# Main.net
KiCad netlist of a schematic drawn in Altium Designer
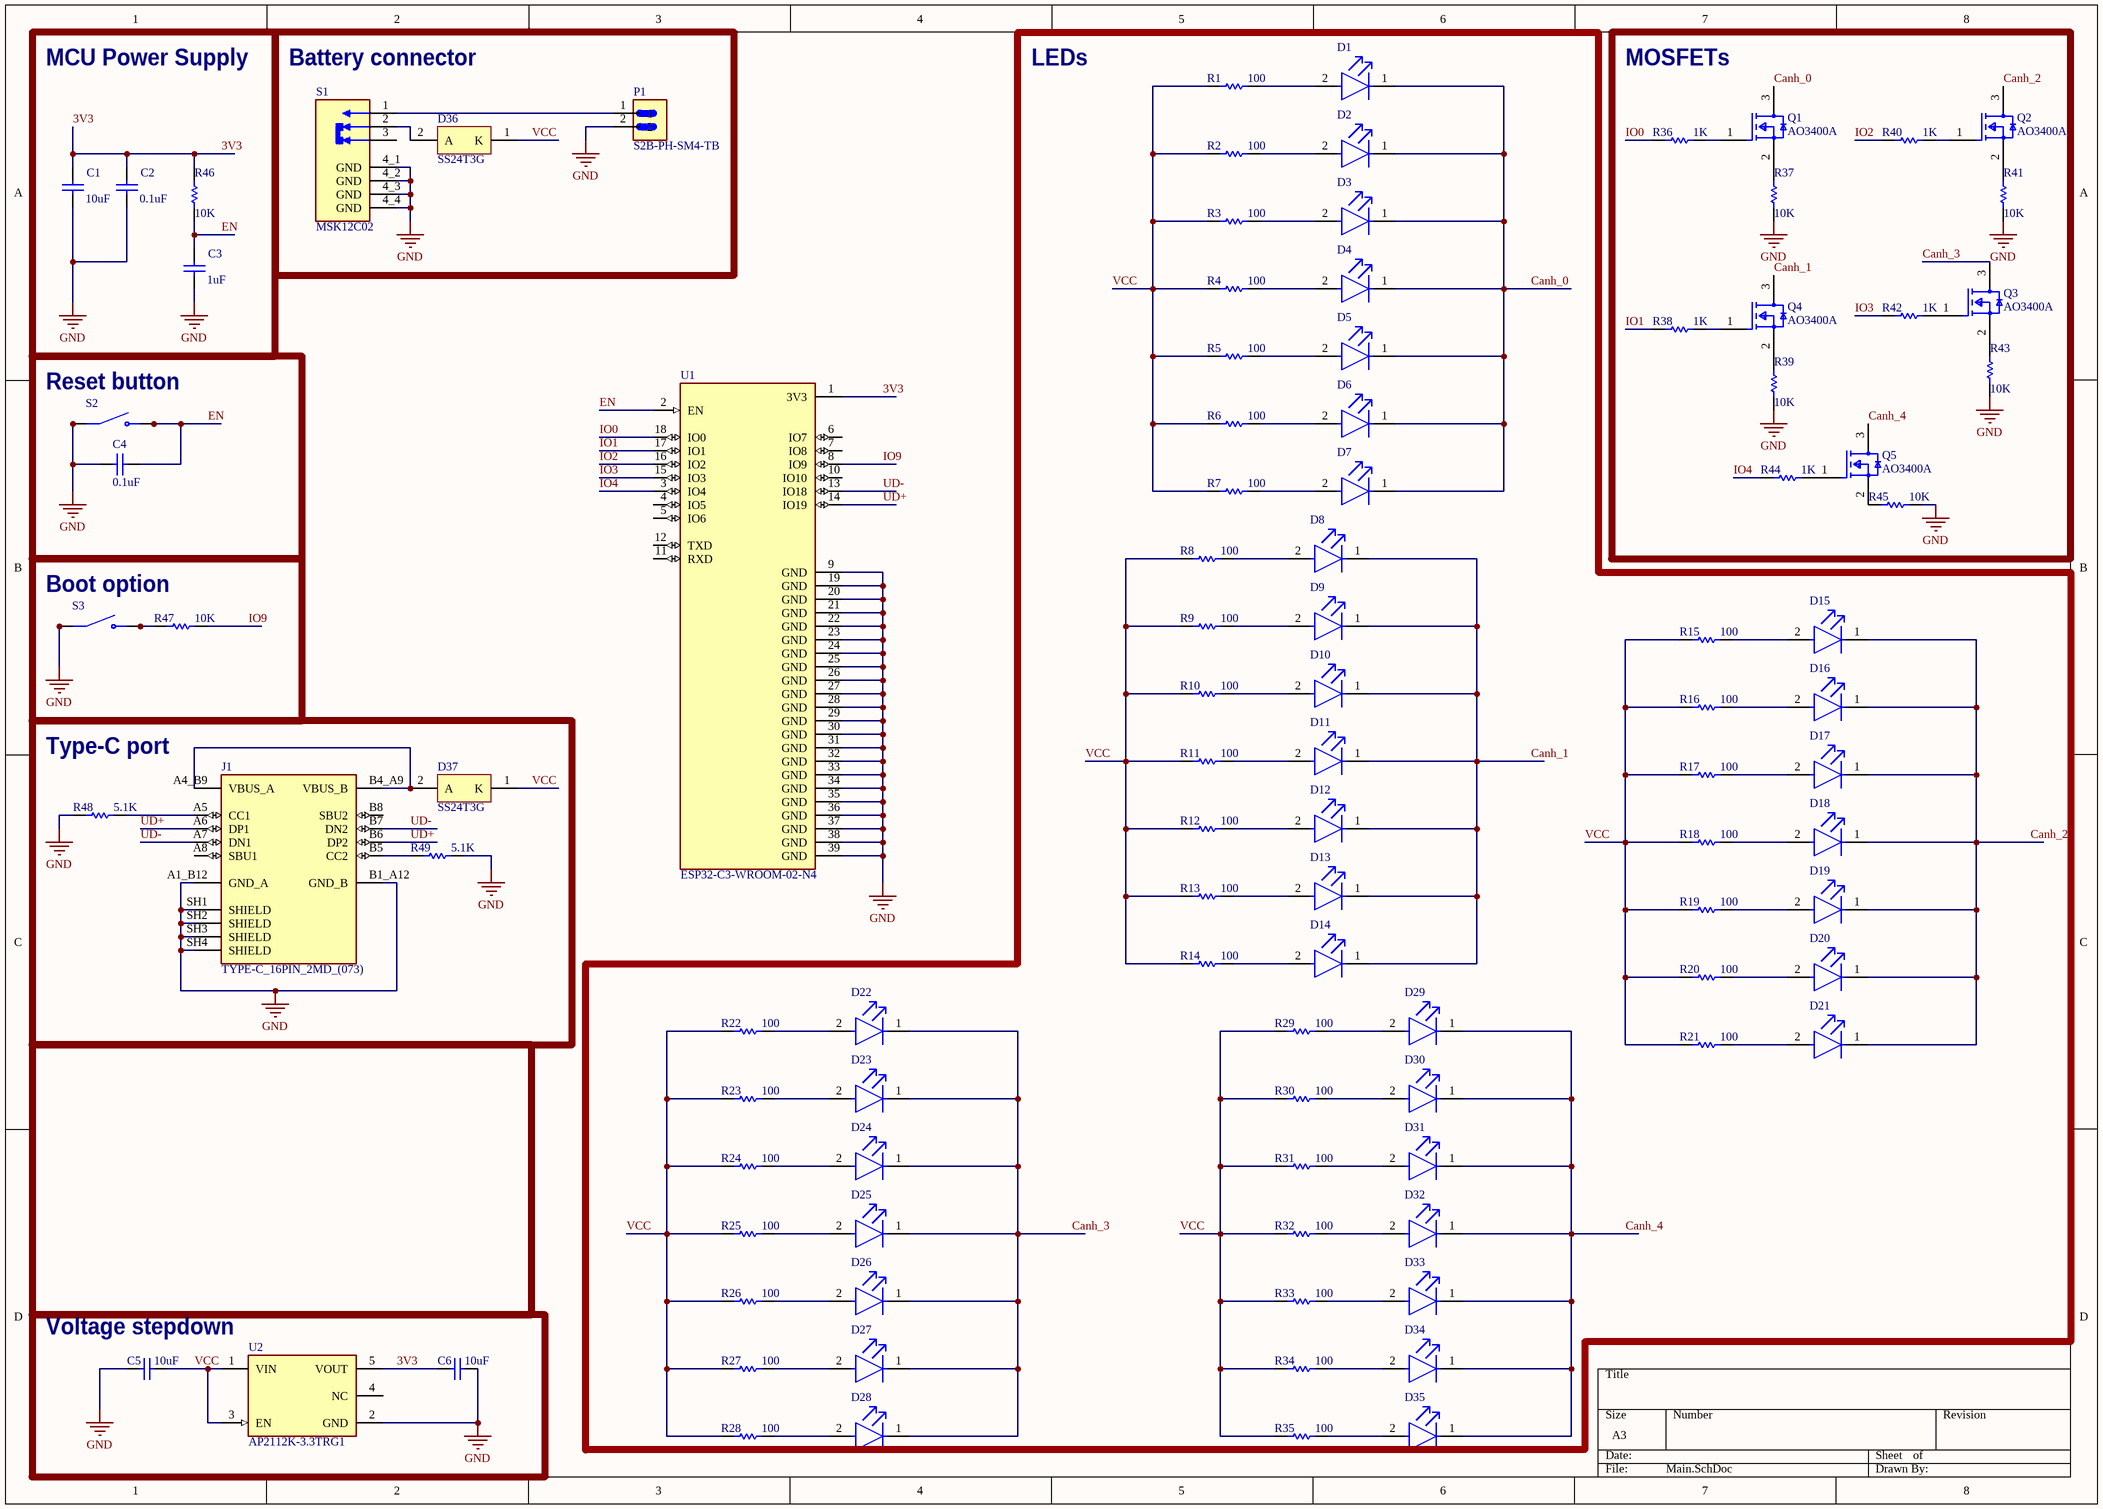
[diagram p0: Main.SchDoc]

(export (version "E")
  (design (tool "Eeschema 10.0.6"))
  (components
    (comp (ref "C1")
      (value "10uF")
      (footprint "1608[0603]cap")
      (description "Capacitor (Semiconductor SIM Model)")
      (fields (field (name "Comment") "Cap Semi") (field (name "PUBLISHER") "Altium Limited"))
      (libsource (lib "smartmcu") (part "Cap Semi"))
    )
    (comp (ref "C2")
      (value "0.1uF")
      (footprint "1608[0603]cap")
      (description "Capacitor (Semiconductor SIM Model)")
      (fields (field (name "Comment") "Cap Semi") (field (name "PUBLISHER") "Altium Limited"))
      (libsource (lib "smartmcu") (part "Cap Semi"))
    )
    (comp (ref "C3")
      (value "1uF")
      (footprint "1608[0603]cap")
      (description "Capacitor (Semiconductor SIM Model)")
      (fields (field (name "Comment") "Cap Semi") (field (name "PUBLISHER") "Altium Limited"))
      (libsource (lib "smartmcu") (part "Cap Semi"))
    )
    (comp (ref "C4")
      (value "0.1uF")
      (footprint "1608[0603]cap")
      (description "Capacitor (Semiconductor SIM Model)")
      (fields (field (name "Comment") "Cap Semi") (field (name "PUBLISHER") "Altium Limited"))
      (libsource (lib "smartmcu") (part "Cap Semi"))
    )
    (comp (ref "C5")
      (value "10uF")
      (footprint "1608[0603]cap")
      (description "Capacitor (Semiconductor SIM Model)")
      (fields (field (name "Comment") "Cap Semi") (field (name "PUBLISHER") "Altium Limited"))
      (libsource (lib "smartmcu") (part "Cap Semi"))
    )
    (comp (ref "C6")
      (value "10uF")
      (footprint "1608[0603]cap")
      (description "Capacitor (Semiconductor SIM Model)")
      (fields (field (name "Comment") "Cap Semi") (field (name "PUBLISHER") "Altium Limited"))
      (libsource (lib "smartmcu") (part "Cap Semi"))
    )
    (comp (ref "D1")
      (value "SSL-LX5093YD")
      (footprint "FP-SSL-LX5093YD-MFG")
      (description "LED YELLOW DIFFUSED T-1 3/4 T/H")
      (libsource (lib "Altium Content Vault") (part "8706943c75ba83719d021d2fdc84c58"))
    )
    (comp (ref "D2")
      (value "SSL-LX5093YD")
      (footprint "FP-SSL-LX5093YD-MFG")
      (description "LED YELLOW DIFFUSED T-1 3/4 T/H")
      (libsource (lib "Altium Content Vault") (part "8706943c75ba83719d021d2fdc84c58"))
    )
    (comp (ref "D3")
      (value "SSL-LX5093YD")
      (footprint "FP-SSL-LX5093YD-MFG")
      (description "LED YELLOW DIFFUSED T-1 3/4 T/H")
      (libsource (lib "Altium Content Vault") (part "8706943c75ba83719d021d2fdc84c58"))
    )
    (comp (ref "D4")
      (value "SSL-LX5093YD")
      (footprint "FP-SSL-LX5093YD-MFG")
      (description "LED YELLOW DIFFUSED T-1 3/4 T/H")
      (libsource (lib "Altium Content Vault") (part "8706943c75ba83719d021d2fdc84c58"))
    )
    (comp (ref "D5")
      (value "SSL-LX5093YD")
      (footprint "FP-SSL-LX5093YD-MFG")
      (description "LED YELLOW DIFFUSED T-1 3/4 T/H")
      (libsource (lib "Altium Content Vault") (part "8706943c75ba83719d021d2fdc84c58"))
    )
    (comp (ref "D6")
      (value "SSL-LX5093YD")
      (footprint "FP-SSL-LX5093YD-MFG")
      (description "LED YELLOW DIFFUSED T-1 3/4 T/H")
      (libsource (lib "Altium Content Vault") (part "8706943c75ba83719d021d2fdc84c58"))
    )
    (comp (ref "D7")
      (value "SSL-LX5093YD")
      (footprint "FP-SSL-LX5093YD-MFG")
      (description "LED YELLOW DIFFUSED T-1 3/4 T/H")
      (libsource (lib "Altium Content Vault") (part "8706943c75ba83719d021d2fdc84c58"))
    )
    (comp (ref "D8")
      (value "SSL-LX5093YD")
      (footprint "FP-SSL-LX5093YD-MFG")
      (description "LED YELLOW DIFFUSED T-1 3/4 T/H")
      (libsource (lib "Altium Content Vault") (part "8706943c75ba83719d021d2fdc84c58"))
    )
    (comp (ref "D9")
      (value "SSL-LX5093YD")
      (footprint "FP-SSL-LX5093YD-MFG")
      (description "LED YELLOW DIFFUSED T-1 3/4 T/H")
      (libsource (lib "Altium Content Vault") (part "8706943c75ba83719d021d2fdc84c58"))
    )
    (comp (ref "D10")
      (value "SSL-LX5093YD")
      (footprint "FP-SSL-LX5093YD-MFG")
      (description "LED YELLOW DIFFUSED T-1 3/4 T/H")
      (libsource (lib "Altium Content Vault") (part "8706943c75ba83719d021d2fdc84c58"))
    )
    (comp (ref "D11")
      (value "SSL-LX5093YD")
      (footprint "FP-SSL-LX5093YD-MFG")
      (description "LED YELLOW DIFFUSED T-1 3/4 T/H")
      (libsource (lib "Altium Content Vault") (part "8706943c75ba83719d021d2fdc84c58"))
    )
    (comp (ref "D12")
      (value "SSL-LX5093YD")
      (footprint "FP-SSL-LX5093YD-MFG")
      (description "LED YELLOW DIFFUSED T-1 3/4 T/H")
      (libsource (lib "Altium Content Vault") (part "8706943c75ba83719d021d2fdc84c58"))
    )
    (comp (ref "D13")
      (value "SSL-LX5093YD")
      (footprint "FP-SSL-LX5093YD-MFG")
      (description "LED YELLOW DIFFUSED T-1 3/4 T/H")
      (libsource (lib "Altium Content Vault") (part "8706943c75ba83719d021d2fdc84c58"))
    )
    (comp (ref "D14")
      (value "SSL-LX5093YD")
      (footprint "FP-SSL-LX5093YD-MFG")
      (description "LED YELLOW DIFFUSED T-1 3/4 T/H")
      (libsource (lib "Altium Content Vault") (part "8706943c75ba83719d021d2fdc84c58"))
    )
    (comp (ref "D15")
      (value "SSL-LX5093YD")
      (footprint "FP-SSL-LX5093YD-MFG")
      (description "LED YELLOW DIFFUSED T-1 3/4 T/H")
      (libsource (lib "Altium Content Vault") (part "8706943c75ba83719d021d2fdc84c58"))
    )
    (comp (ref "D16")
      (value "SSL-LX5093YD")
      (footprint "FP-SSL-LX5093YD-MFG")
      (description "LED YELLOW DIFFUSED T-1 3/4 T/H")
      (libsource (lib "Altium Content Vault") (part "8706943c75ba83719d021d2fdc84c58"))
    )
    (comp (ref "D17")
      (value "SSL-LX5093YD")
      (footprint "FP-SSL-LX5093YD-MFG")
      (description "LED YELLOW DIFFUSED T-1 3/4 T/H")
      (libsource (lib "Altium Content Vault") (part "8706943c75ba83719d021d2fdc84c58"))
    )
    (comp (ref "D18")
      (value "SSL-LX5093YD")
      (footprint "FP-SSL-LX5093YD-MFG")
      (description "LED YELLOW DIFFUSED T-1 3/4 T/H")
      (libsource (lib "Altium Content Vault") (part "8706943c75ba83719d021d2fdc84c58"))
    )
    (comp (ref "D19")
      (value "SSL-LX5093YD")
      (footprint "FP-SSL-LX5093YD-MFG")
      (description "LED YELLOW DIFFUSED T-1 3/4 T/H")
      (libsource (lib "Altium Content Vault") (part "8706943c75ba83719d021d2fdc84c58"))
    )
    (comp (ref "D20")
      (value "SSL-LX5093YD")
      (footprint "FP-SSL-LX5093YD-MFG")
      (description "LED YELLOW DIFFUSED T-1 3/4 T/H")
      (libsource (lib "Altium Content Vault") (part "8706943c75ba83719d021d2fdc84c58"))
    )
    (comp (ref "D21")
      (value "SSL-LX5093YD")
      (footprint "FP-SSL-LX5093YD-MFG")
      (description "LED YELLOW DIFFUSED T-1 3/4 T/H")
      (libsource (lib "Altium Content Vault") (part "8706943c75ba83719d021d2fdc84c58"))
    )
    (comp (ref "D22")
      (value "SSL-LX5093YD")
      (footprint "FP-SSL-LX5093YD-MFG")
      (description "LED YELLOW DIFFUSED T-1 3/4 T/H")
      (libsource (lib "Altium Content Vault") (part "8706943c75ba83719d021d2fdc84c58"))
    )
    (comp (ref "D23")
      (value "SSL-LX5093YD")
      (footprint "FP-SSL-LX5093YD-MFG")
      (description "LED YELLOW DIFFUSED T-1 3/4 T/H")
      (libsource (lib "Altium Content Vault") (part "8706943c75ba83719d021d2fdc84c58"))
    )
    (comp (ref "D24")
      (value "SSL-LX5093YD")
      (footprint "FP-SSL-LX5093YD-MFG")
      (description "LED YELLOW DIFFUSED T-1 3/4 T/H")
      (libsource (lib "Altium Content Vault") (part "8706943c75ba83719d021d2fdc84c58"))
    )
    (comp (ref "D25")
      (value "SSL-LX5093YD")
      (footprint "FP-SSL-LX5093YD-MFG")
      (description "LED YELLOW DIFFUSED T-1 3/4 T/H")
      (libsource (lib "Altium Content Vault") (part "8706943c75ba83719d021d2fdc84c58"))
    )
    (comp (ref "D26")
      (value "SSL-LX5093YD")
      (footprint "FP-SSL-LX5093YD-MFG")
      (description "LED YELLOW DIFFUSED T-1 3/4 T/H")
      (libsource (lib "Altium Content Vault") (part "8706943c75ba83719d021d2fdc84c58"))
    )
    (comp (ref "D27")
      (value "SSL-LX5093YD")
      (footprint "FP-SSL-LX5093YD-MFG")
      (description "LED YELLOW DIFFUSED T-1 3/4 T/H")
      (libsource (lib "Altium Content Vault") (part "8706943c75ba83719d021d2fdc84c58"))
    )
    (comp (ref "D28")
      (value "SSL-LX5093YD")
      (footprint "FP-SSL-LX5093YD-MFG")
      (description "LED YELLOW DIFFUSED T-1 3/4 T/H")
      (libsource (lib "Altium Content Vault") (part "8706943c75ba83719d021d2fdc84c58"))
    )
    (comp (ref "D29")
      (value "SSL-LX5093YD")
      (footprint "FP-SSL-LX5093YD-MFG")
      (description "LED YELLOW DIFFUSED T-1 3/4 T/H")
      (libsource (lib "Altium Content Vault") (part "8706943c75ba83719d021d2fdc84c58"))
    )
    (comp (ref "D30")
      (value "SSL-LX5093YD")
      (footprint "FP-SSL-LX5093YD-MFG")
      (description "LED YELLOW DIFFUSED T-1 3/4 T/H")
      (libsource (lib "Altium Content Vault") (part "8706943c75ba83719d021d2fdc84c58"))
    )
    (comp (ref "D31")
      (value "SSL-LX5093YD")
      (footprint "FP-SSL-LX5093YD-MFG")
      (description "LED YELLOW DIFFUSED T-1 3/4 T/H")
      (libsource (lib "Altium Content Vault") (part "8706943c75ba83719d021d2fdc84c58"))
    )
    (comp (ref "D32")
      (value "SSL-LX5093YD")
      (footprint "FP-SSL-LX5093YD-MFG")
      (description "LED YELLOW DIFFUSED T-1 3/4 T/H")
      (libsource (lib "Altium Content Vault") (part "8706943c75ba83719d021d2fdc84c58"))
    )
    (comp (ref "D33")
      (value "SSL-LX5093YD")
      (footprint "FP-SSL-LX5093YD-MFG")
      (description "LED YELLOW DIFFUSED T-1 3/4 T/H")
      (libsource (lib "Altium Content Vault") (part "8706943c75ba83719d021d2fdc84c58"))
    )
    (comp (ref "D34")
      (value "SSL-LX5093YD")
      (footprint "FP-SSL-LX5093YD-MFG")
      (description "LED YELLOW DIFFUSED T-1 3/4 T/H")
      (libsource (lib "Altium Content Vault") (part "8706943c75ba83719d021d2fdc84c58"))
    )
    (comp (ref "D35")
      (value "SSL-LX5093YD")
      (footprint "FP-SSL-LX5093YD-MFG")
      (description "LED YELLOW DIFFUSED T-1 3/4 T/H")
      (libsource (lib "Altium Content Vault") (part "8706943c75ba83719d021d2fdc84c58"))
    )
    (comp (ref "D36")
      (value "SS24T3G")
      (footprint "ONSC-SMB-2-403A-03_V")
      (description "Schottky Power Rectifier, 2-Pin SMB, Pb-Free, Tape and Reel")
      (fields (field (name "MANUFACTURER") "On Semiconductor"))
      (libsource (lib "Altium Content Vault") (part "ONSC-D-K1A2-2_A"))
    )
    (comp (ref "D37")
      (value "SS24T3G")
      (footprint "ONSC-SMB-2-403A-03_V")
      (description "Schottky Power Rectifier, 2-Pin SMB, Pb-Free, Tape and Reel")
      (fields (field (name "MANUFACTURER") "On Semiconductor"))
      (libsource (lib "Altium Content Vault") (part "ONSC-D-K1A2-2_A"))
    )
    (comp (ref "J1")
      (value "TYPE-C_16PIN_2MD_(073)")
      (footprint "SHOUHAN_TYPE-C_16PIN_2MD_(073)")
      (description "DC-5V 5A Type C USB")
      (fields (field (name "MF") "Shouhan") (field (name "MP") "TYPE-C 16PIN 2MD (073)"))
      (libsource (lib "TYPE-C_16PIN_2MD__073_") (part "TYPE-C_16PIN_2MD_(073)"))
    )
    (comp (ref "P1")
      (value "S2B-PH-SM4-TB")
      (footprint "JST_S2B-PH-SM4-TB")
      (description "Connector Header Surface Mount, Right Angle 2 position 0.079 (2.00mm)")
      (fields (field (name "MF") "JST Sales"))
      (libsource (lib "S2B-PH-SM4-TB") (part "S2B-PH-SM4-TB"))
    )
    (comp (ref "Q1")
      (value "AO3400A")
      (footprint "FP-SOT23-MFG")
      (description "MOSFET N-CH 30V 5.7A SOT23")
      (libsource (lib "Altium Content Vault") (part "0a9ea7c96deaaede766a5b531c28de0"))
    )
    (comp (ref "Q2")
      (value "AO3400A")
      (footprint "FP-SOT23-MFG")
      (description "MOSFET N-CH 30V 5.7A SOT23")
      (libsource (lib "Altium Content Vault") (part "0a9ea7c96deaaede766a5b531c28de0"))
    )
    (comp (ref "Q3")
      (value "AO3400A")
      (footprint "FP-SOT23-MFG")
      (description "MOSFET N-CH 30V 5.7A SOT23")
      (libsource (lib "Altium Content Vault") (part "0a9ea7c96deaaede766a5b531c28de0"))
    )
    (comp (ref "Q4")
      (value "AO3400A")
      (footprint "FP-SOT23-MFG")
      (description "MOSFET N-CH 30V 5.7A SOT23")
      (libsource (lib "Altium Content Vault") (part "0a9ea7c96deaaede766a5b531c28de0"))
    )
    (comp (ref "Q5")
      (value "AO3400A")
      (footprint "FP-SOT23-MFG")
      (description "MOSFET N-CH 30V 5.7A SOT23")
      (libsource (lib "Altium Content Vault") (part "0a9ea7c96deaaede766a5b531c28de0"))
    )
    (comp (ref "R1")
      (value "100")
      (footprint "MY_0603")
      (description "Standard resistor")
      (fields (field (name "ASID PART NUMBER") "Res-AS"))
      (libsource (lib "smartmcu") (part "Res"))
    )
    (comp (ref "R2")
      (value "100")
      (footprint "MY_0603")
      (description "Standard resistor")
      (fields (field (name "ASID PART NUMBER") "Res-AS"))
      (libsource (lib "smartmcu") (part "Res"))
    )
    (comp (ref "R3")
      (value "100")
      (footprint "MY_0603")
      (description "Standard resistor")
      (fields (field (name "ASID PART NUMBER") "Res-AS"))
      (libsource (lib "smartmcu") (part "Res"))
    )
    (comp (ref "R4")
      (value "100")
      (footprint "MY_0603")
      (description "Standard resistor")
      (fields (field (name "ASID PART NUMBER") "Res-AS"))
      (libsource (lib "smartmcu") (part "Res"))
    )
    (comp (ref "R5")
      (value "100")
      (footprint "MY_0603")
      (description "Standard resistor")
      (fields (field (name "ASID PART NUMBER") "Res-AS"))
      (libsource (lib "smartmcu") (part "Res"))
    )
    (comp (ref "R6")
      (value "100")
      (footprint "MY_0603")
      (description "Standard resistor")
      (fields (field (name "ASID PART NUMBER") "Res-AS"))
      (libsource (lib "smartmcu") (part "Res"))
    )
    (comp (ref "R7")
      (value "100")
      (footprint "MY_0603")
      (description "Standard resistor")
      (fields (field (name "ASID PART NUMBER") "Res-AS"))
      (libsource (lib "smartmcu") (part "Res"))
    )
    (comp (ref "R8")
      (value "100")
      (footprint "MY_0603")
      (description "Standard resistor")
      (fields (field (name "ASID PART NUMBER") "Res-AS"))
      (libsource (lib "smartmcu") (part "Res"))
    )
    (comp (ref "R9")
      (value "100")
      (footprint "MY_0603")
      (description "Standard resistor")
      (fields (field (name "ASID PART NUMBER") "Res-AS"))
      (libsource (lib "smartmcu") (part "Res"))
    )
    (comp (ref "R10")
      (value "100")
      (footprint "MY_0603")
      (description "Standard resistor")
      (fields (field (name "ASID PART NUMBER") "Res-AS"))
      (libsource (lib "smartmcu") (part "Res"))
    )
    (comp (ref "R11")
      (value "100")
      (footprint "MY_0603")
      (description "Standard resistor")
      (fields (field (name "ASID PART NUMBER") "Res-AS"))
      (libsource (lib "smartmcu") (part "Res"))
    )
    (comp (ref "R12")
      (value "100")
      (footprint "MY_0603")
      (description "Standard resistor")
      (fields (field (name "ASID PART NUMBER") "Res-AS"))
      (libsource (lib "smartmcu") (part "Res"))
    )
    (comp (ref "R13")
      (value "100")
      (footprint "MY_0603")
      (description "Standard resistor")
      (fields (field (name "ASID PART NUMBER") "Res-AS"))
      (libsource (lib "smartmcu") (part "Res"))
    )
    (comp (ref "R14")
      (value "100")
      (footprint "MY_0603")
      (description "Standard resistor")
      (fields (field (name "ASID PART NUMBER") "Res-AS"))
      (libsource (lib "smartmcu") (part "Res"))
    )
    (comp (ref "R15")
      (value "100")
      (footprint "MY_0603")
      (description "Standard resistor")
      (fields (field (name "ASID PART NUMBER") "Res-AS"))
      (libsource (lib "smartmcu") (part "Res"))
    )
    (comp (ref "R16")
      (value "100")
      (footprint "MY_0603")
      (description "Standard resistor")
      (fields (field (name "ASID PART NUMBER") "Res-AS"))
      (libsource (lib "smartmcu") (part "Res"))
    )
    (comp (ref "R17")
      (value "100")
      (footprint "MY_0603")
      (description "Standard resistor")
      (fields (field (name "ASID PART NUMBER") "Res-AS"))
      (libsource (lib "smartmcu") (part "Res"))
    )
    (comp (ref "R18")
      (value "100")
      (footprint "MY_0603")
      (description "Standard resistor")
      (fields (field (name "ASID PART NUMBER") "Res-AS"))
      (libsource (lib "smartmcu") (part "Res"))
    )
    (comp (ref "R19")
      (value "100")
      (footprint "MY_0603")
      (description "Standard resistor")
      (fields (field (name "ASID PART NUMBER") "Res-AS"))
      (libsource (lib "smartmcu") (part "Res"))
    )
    (comp (ref "R20")
      (value "100")
      (footprint "MY_0603")
      (description "Standard resistor")
      (fields (field (name "ASID PART NUMBER") "Res-AS"))
      (libsource (lib "smartmcu") (part "Res"))
    )
    (comp (ref "R21")
      (value "100")
      (footprint "MY_0603")
      (description "Standard resistor")
      (fields (field (name "ASID PART NUMBER") "Res-AS"))
      (libsource (lib "smartmcu") (part "Res"))
    )
    (comp (ref "R22")
      (value "100")
      (footprint "MY_0603")
      (description "Standard resistor")
      (fields (field (name "ASID PART NUMBER") "Res-AS"))
      (libsource (lib "smartmcu") (part "Res"))
    )
    (comp (ref "R23")
      (value "100")
      (footprint "MY_0603")
      (description "Standard resistor")
      (fields (field (name "ASID PART NUMBER") "Res-AS"))
      (libsource (lib "smartmcu") (part "Res"))
    )
    (comp (ref "R24")
      (value "100")
      (footprint "MY_0603")
      (description "Standard resistor")
      (fields (field (name "ASID PART NUMBER") "Res-AS"))
      (libsource (lib "smartmcu") (part "Res"))
    )
    (comp (ref "R25")
      (value "100")
      (footprint "MY_0603")
      (description "Standard resistor")
      (fields (field (name "ASID PART NUMBER") "Res-AS"))
      (libsource (lib "smartmcu") (part "Res"))
    )
    (comp (ref "R26")
      (value "100")
      (footprint "MY_0603")
      (description "Standard resistor")
      (fields (field (name "ASID PART NUMBER") "Res-AS"))
      (libsource (lib "smartmcu") (part "Res"))
    )
    (comp (ref "R27")
      (value "100")
      (footprint "MY_0603")
      (description "Standard resistor")
      (fields (field (name "ASID PART NUMBER") "Res-AS"))
      (libsource (lib "smartmcu") (part "Res"))
    )
    (comp (ref "R28")
      (value "100")
      (footprint "MY_0603")
      (description "Standard resistor")
      (fields (field (name "ASID PART NUMBER") "Res-AS"))
      (libsource (lib "smartmcu") (part "Res"))
    )
    (comp (ref "R29")
      (value "100")
      (footprint "MY_0603")
      (description "Standard resistor")
      (fields (field (name "ASID PART NUMBER") "Res-AS"))
      (libsource (lib "smartmcu") (part "Res"))
    )
    (comp (ref "R30")
      (value "100")
      (footprint "MY_0603")
      (description "Standard resistor")
      (fields (field (name "ASID PART NUMBER") "Res-AS"))
      (libsource (lib "smartmcu") (part "Res"))
    )
    (comp (ref "R31")
      (value "100")
      (footprint "MY_0603")
      (description "Standard resistor")
      (fields (field (name "ASID PART NUMBER") "Res-AS"))
      (libsource (lib "smartmcu") (part "Res"))
    )
    (comp (ref "R32")
      (value "100")
      (footprint "MY_0603")
      (description "Standard resistor")
      (fields (field (name "ASID PART NUMBER") "Res-AS"))
      (libsource (lib "smartmcu") (part "Res"))
    )
    (comp (ref "R33")
      (value "100")
      (footprint "MY_0603")
      (description "Standard resistor")
      (fields (field (name "ASID PART NUMBER") "Res-AS"))
      (libsource (lib "smartmcu") (part "Res"))
    )
    (comp (ref "R34")
      (value "100")
      (footprint "MY_0603")
      (description "Standard resistor")
      (fields (field (name "ASID PART NUMBER") "Res-AS"))
      (libsource (lib "smartmcu") (part "Res"))
    )
    (comp (ref "R35")
      (value "100")
      (footprint "MY_0603")
      (description "Standard resistor")
      (fields (field (name "ASID PART NUMBER") "Res-AS"))
      (libsource (lib "smartmcu") (part "Res"))
    )
    (comp (ref "R36")
      (value "1K")
      (footprint "MY_0603")
      (description "Standard resistor")
      (fields (field (name "ASID PART NUMBER") "Res-AS"))
      (libsource (lib "smartmcu") (part "Res"))
    )
    (comp (ref "R37")
      (value "10K")
      (footprint "MY_0603")
      (description "Standard resistor")
      (fields (field (name "ASID PART NUMBER") "Res-AS"))
      (libsource (lib "smartmcu") (part "Res"))
    )
    (comp (ref "R38")
      (value "1K")
      (footprint "MY_0603")
      (description "Standard resistor")
      (fields (field (name "ASID PART NUMBER") "Res-AS"))
      (libsource (lib "smartmcu") (part "Res"))
    )
    (comp (ref "R39")
      (value "10K")
      (footprint "MY_0603")
      (description "Standard resistor")
      (fields (field (name "ASID PART NUMBER") "Res-AS"))
      (libsource (lib "smartmcu") (part "Res"))
    )
    (comp (ref "R40")
      (value "1K")
      (footprint "MY_0603")
      (description "Standard resistor")
      (fields (field (name "ASID PART NUMBER") "Res-AS"))
      (libsource (lib "smartmcu") (part "Res"))
    )
    (comp (ref "R41")
      (value "10K")
      (footprint "MY_0603")
      (description "Standard resistor")
      (fields (field (name "ASID PART NUMBER") "Res-AS"))
      (libsource (lib "smartmcu") (part "Res"))
    )
    (comp (ref "R42")
      (value "1K")
      (footprint "MY_0603")
      (description "Standard resistor")
      (fields (field (name "ASID PART NUMBER") "Res-AS"))
      (libsource (lib "smartmcu") (part "Res"))
    )
    (comp (ref "R43")
      (value "10K")
      (footprint "MY_0603")
      (description "Standard resistor")
      (fields (field (name "ASID PART NUMBER") "Res-AS"))
      (libsource (lib "smartmcu") (part "Res"))
    )
    (comp (ref "R44")
      (value "1K")
      (footprint "MY_0603")
      (description "Standard resistor")
      (fields (field (name "ASID PART NUMBER") "Res-AS"))
      (libsource (lib "smartmcu") (part "Res"))
    )
    (comp (ref "R45")
      (value "10K")
      (footprint "MY_0603")
      (description "Standard resistor")
      (fields (field (name "ASID PART NUMBER") "Res-AS"))
      (libsource (lib "smartmcu") (part "Res"))
    )
    (comp (ref "R46")
      (value "10K")
      (footprint "MY_0603")
      (description "Standard resistor")
      (fields (field (name "ASID PART NUMBER") "Res-AS"))
      (libsource (lib "smartmcu") (part "Res"))
    )
    (comp (ref "R47")
      (value "10K")
      (footprint "MY_0603")
      (description "Standard resistor")
      (fields (field (name "ASID PART NUMBER") "Res-AS"))
      (libsource (lib "smartmcu") (part "Res"))
    )
    (comp (ref "R48")
      (value "5.1K")
      (footprint "MY_0603")
      (description "Standard resistor")
      (fields (field (name "ASID PART NUMBER") "Res-AS"))
      (libsource (lib "smartmcu") (part "Res"))
    )
    (comp (ref "R49")
      (value "5.1K")
      (footprint "MY_0603")
      (description "Standard resistor")
      (fields (field (name "ASID PART NUMBER") "Res-AS"))
      (libsource (lib "smartmcu") (part "Res"))
    )
    (comp (ref "S1")
      (value "MSK12C02")
      (footprint "SW_MSK12C02")
      (libsource (lib "MSK12C02") (part "MSK12C02"))
    )
    (comp (ref "S2")
      (value "1571527-2")
      (footprint "SW_1571527-2")
      (description "Switch Tactile OFF (ON) SPST Round Button Gull Wing 0.05A 24VDC 0.98N SMD T/R")
      (fields (field (name "MF") "TE Connectivity"))
      (libsource (lib "1571527-2") (part "1571527-2"))
    )
    (comp (ref "S3")
      (value "1571527-2")
      (footprint "SW_1571527-2")
      (description "Switch Tactile OFF (ON) SPST Round Button Gull Wing 0.05A 24VDC 0.98N SMD T/R")
      (fields (field (name "MF") "TE Connectivity"))
      (libsource (lib "1571527-2") (part "1571527-2"))
    )
    (comp (ref "U1")
      (value "ESP32-C3-WROOM-02-N4")
      (footprint "MODULE_ESP32-C3-WROOM-02-H4")
      (fields (field (name "MF") "Espressif Systems"))
      (libsource (lib "ESP32-C3-WROOM-02-N4") (part "ESP32-C3-WROOM-02-N4"))
    )
    (comp (ref "U2")
      (value "AP2112K-3.3TRG1")
      (footprint "FP-SOT25-IPC_A")
      (description "IC REG LINEAR 3.3V 600MA SOT25")
      (libsource (lib "Altium Content Vault") (part "c8ab751aee5229183125ab046a11caa"))
    )
  )
  (nets
    (net (code "1") (name "/3V3") (class "Default")
      (node (ref "C1") (pin "2") (pinfunction "2_2") (pintype "passive"))
      (node (ref "C2") (pin "2") (pinfunction "2_2") (pintype "passive"))
      (node (ref "C6") (pin "2") (pinfunction "2_2") (pintype "passive"))
      (node (ref "R46") (pin "2") (pinfunction "2_2") (pintype "passive"))
      (node (ref "U1") (pin "1") (pinfunction "3V3_1") (pintype "power_in"))
      (node (ref "U2") (pin "5") (pinfunction "VOUT_5") (pintype "power_in"))
    )
    (net (code "2") (name "/Canh_0") (class "Default")
      (node (ref "D1") (pin "1") (pinfunction "C_1") (pintype "passive"))
      (node (ref "D2") (pin "1") (pinfunction "C_1") (pintype "passive"))
      (node (ref "D3") (pin "1") (pinfunction "C_1") (pintype "passive"))
      (node (ref "D4") (pin "1") (pinfunction "C_1") (pintype "passive"))
      (node (ref "D5") (pin "1") (pinfunction "C_1") (pintype "passive"))
      (node (ref "D6") (pin "1") (pinfunction "C_1") (pintype "passive"))
      (node (ref "D7") (pin "1") (pinfunction "C_1") (pintype "passive"))
      (node (ref "Q1") (pin "3") (pinfunction "D_3") (pintype "passive"))
    )
    (net (code "3") (name "/Canh_1") (class "Default")
      (node (ref "D10") (pin "1") (pinfunction "C_1") (pintype "passive"))
      (node (ref "D11") (pin "1") (pinfunction "C_1") (pintype "passive"))
      (node (ref "D12") (pin "1") (pinfunction "C_1") (pintype "passive"))
      (node (ref "D13") (pin "1") (pinfunction "C_1") (pintype "passive"))
      (node (ref "D14") (pin "1") (pinfunction "C_1") (pintype "passive"))
      (node (ref "D8") (pin "1") (pinfunction "C_1") (pintype "passive"))
      (node (ref "D9") (pin "1") (pinfunction "C_1") (pintype "passive"))
      (node (ref "Q4") (pin "3") (pinfunction "D_3") (pintype "passive"))
    )
    (net (code "4") (name "/Canh_2") (class "Default")
      (node (ref "D15") (pin "1") (pinfunction "C_1") (pintype "passive"))
      (node (ref "D16") (pin "1") (pinfunction "C_1") (pintype "passive"))
      (node (ref "D17") (pin "1") (pinfunction "C_1") (pintype "passive"))
      (node (ref "D18") (pin "1") (pinfunction "C_1") (pintype "passive"))
      (node (ref "D19") (pin "1") (pinfunction "C_1") (pintype "passive"))
      (node (ref "D20") (pin "1") (pinfunction "C_1") (pintype "passive"))
      (node (ref "D21") (pin "1") (pinfunction "C_1") (pintype "passive"))
      (node (ref "Q2") (pin "3") (pinfunction "D_3") (pintype "passive"))
    )
    (net (code "5") (name "/Canh_3") (class "Default")
      (node (ref "D22") (pin "1") (pinfunction "C_1") (pintype "passive"))
      (node (ref "D23") (pin "1") (pinfunction "C_1") (pintype "passive"))
      (node (ref "D24") (pin "1") (pinfunction "C_1") (pintype "passive"))
      (node (ref "D25") (pin "1") (pinfunction "C_1") (pintype "passive"))
      (node (ref "D26") (pin "1") (pinfunction "C_1") (pintype "passive"))
      (node (ref "D27") (pin "1") (pinfunction "C_1") (pintype "passive"))
      (node (ref "D28") (pin "1") (pinfunction "C_1") (pintype "passive"))
      (node (ref "Q3") (pin "3") (pinfunction "D_3") (pintype "passive"))
    )
    (net (code "6") (name "/Canh_4") (class "Default")
      (node (ref "D29") (pin "1") (pinfunction "C_1") (pintype "passive"))
      (node (ref "D30") (pin "1") (pinfunction "C_1") (pintype "passive"))
      (node (ref "D31") (pin "1") (pinfunction "C_1") (pintype "passive"))
      (node (ref "D32") (pin "1") (pinfunction "C_1") (pintype "passive"))
      (node (ref "D33") (pin "1") (pinfunction "C_1") (pintype "passive"))
      (node (ref "D34") (pin "1") (pinfunction "C_1") (pintype "passive"))
      (node (ref "D35") (pin "1") (pinfunction "C_1") (pintype "passive"))
      (node (ref "Q5") (pin "3") (pinfunction "D_3") (pintype "passive"))
    )
    (net (code "7") (name "/EN") (class "Default")
      (node (ref "C3") (pin "2") (pinfunction "2_2") (pintype "passive"))
      (node (ref "C4") (pin "1") (pinfunction "1_1") (pintype "passive"))
      (node (ref "R46") (pin "1") (pinfunction "1_1") (pintype "passive"))
      (node (ref "S2") (pin "3") (pinfunction "NO_3") (pintype "passive"))
      (node (ref "S2") (pin "4") (pinfunction "NO_4") (pintype "passive"))
      (node (ref "U1") (pin "2") (pinfunction "EN_2") (pintype "input"))
    )
    (net (code "8") (name "/IO0") (class "Default")
      (node (ref "R36") (pin "1") (pinfunction "1_1") (pintype "passive"))
      (node (ref "U1") (pin "18") (pinfunction "IO0_18") (pintype "bidirectional"))
    )
    (net (code "9") (name "/IO1") (class "Default")
      (node (ref "R38") (pin "1") (pinfunction "1_1") (pintype "passive"))
      (node (ref "U1") (pin "17") (pinfunction "IO1_17") (pintype "bidirectional"))
    )
    (net (code "10") (name "/IO2") (class "Default")
      (node (ref "R40") (pin "1") (pinfunction "1_1") (pintype "passive"))
      (node (ref "U1") (pin "16") (pinfunction "IO2_16") (pintype "bidirectional"))
    )
    (net (code "11") (name "/IO3") (class "Default")
      (node (ref "R42") (pin "1") (pinfunction "1_1") (pintype "passive"))
      (node (ref "U1") (pin "15") (pinfunction "IO3_15") (pintype "bidirectional"))
    )
    (net (code "12") (name "/IO4") (class "Default")
      (node (ref "R44") (pin "1") (pinfunction "1_1") (pintype "passive"))
      (node (ref "U1") (pin "3") (pinfunction "IO4_3") (pintype "bidirectional"))
    )
    (net (code "13") (name "/IO9") (class "Default")
      (node (ref "R47") (pin "1") (pinfunction "1_1") (pintype "passive"))
      (node (ref "U1") (pin "8") (pinfunction "IO9_8") (pintype "bidirectional"))
    )
    (net (code "14") (name "/UD+") (class "Default")
      (node (ref "J1") (pin "A6") (pinfunction "DP1_A6") (pintype "bidirectional"))
      (node (ref "J1") (pin "B6") (pinfunction "DP2_B6") (pintype "bidirectional"))
      (node (ref "U1") (pin "14") (pinfunction "IO19_14") (pintype "bidirectional"))
    )
    (net (code "15") (name "/UD-") (class "Default")
      (node (ref "J1") (pin "A7") (pinfunction "DN1_A7") (pintype "bidirectional"))
      (node (ref "J1") (pin "B7") (pinfunction "DN2_B7") (pintype "bidirectional"))
      (node (ref "U1") (pin "13") (pinfunction "IO18_13") (pintype "bidirectional"))
    )
    (net (code "16") (name "/VCC") (class "Default")
      (node (ref "C5") (pin "1") (pinfunction "1_1") (pintype "passive"))
      (node (ref "D36") (pin "1") (pinfunction "K_1") (pintype "passive"))
      (node (ref "D37") (pin "1") (pinfunction "K_1") (pintype "passive"))
      (node (ref "R1") (pin "1") (pinfunction "1_1") (pintype "passive"))
      (node (ref "R10") (pin "1") (pinfunction "1_1") (pintype "passive"))
      (node (ref "R11") (pin "1") (pinfunction "1_1") (pintype "passive"))
      (node (ref "R12") (pin "1") (pinfunction "1_1") (pintype "passive"))
      (node (ref "R13") (pin "1") (pinfunction "1_1") (pintype "passive"))
      (node (ref "R14") (pin "1") (pinfunction "1_1") (pintype "passive"))
      (node (ref "R15") (pin "1") (pinfunction "1_1") (pintype "passive"))
      (node (ref "R16") (pin "1") (pinfunction "1_1") (pintype "passive"))
      (node (ref "R17") (pin "1") (pinfunction "1_1") (pintype "passive"))
      (node (ref "R18") (pin "1") (pinfunction "1_1") (pintype "passive"))
      (node (ref "R19") (pin "1") (pinfunction "1_1") (pintype "passive"))
      (node (ref "R2") (pin "1") (pinfunction "1_1") (pintype "passive"))
      (node (ref "R20") (pin "1") (pinfunction "1_1") (pintype "passive"))
      (node (ref "R21") (pin "1") (pinfunction "1_1") (pintype "passive"))
      (node (ref "R22") (pin "1") (pinfunction "1_1") (pintype "passive"))
      (node (ref "R23") (pin "1") (pinfunction "1_1") (pintype "passive"))
      (node (ref "R24") (pin "1") (pinfunction "1_1") (pintype "passive"))
      (node (ref "R25") (pin "1") (pinfunction "1_1") (pintype "passive"))
      (node (ref "R26") (pin "1") (pinfunction "1_1") (pintype "passive"))
      (node (ref "R27") (pin "1") (pinfunction "1_1") (pintype "passive"))
      (node (ref "R28") (pin "1") (pinfunction "1_1") (pintype "passive"))
      (node (ref "R29") (pin "1") (pinfunction "1_1") (pintype "passive"))
      (node (ref "R3") (pin "1") (pinfunction "1_1") (pintype "passive"))
      (node (ref "R30") (pin "1") (pinfunction "1_1") (pintype "passive"))
      (node (ref "R31") (pin "1") (pinfunction "1_1") (pintype "passive"))
      (node (ref "R32") (pin "1") (pinfunction "1_1") (pintype "passive"))
      (node (ref "R33") (pin "1") (pinfunction "1_1") (pintype "passive"))
      (node (ref "R34") (pin "1") (pinfunction "1_1") (pintype "passive"))
      (node (ref "R35") (pin "1") (pinfunction "1_1") (pintype "passive"))
      (node (ref "R4") (pin "1") (pinfunction "1_1") (pintype "passive"))
      (node (ref "R5") (pin "1") (pinfunction "1_1") (pintype "passive"))
      (node (ref "R6") (pin "1") (pinfunction "1_1") (pintype "passive"))
      (node (ref "R7") (pin "1") (pinfunction "1_1") (pintype "passive"))
      (node (ref "R8") (pin "1") (pinfunction "1_1") (pintype "passive"))
      (node (ref "R9") (pin "1") (pinfunction "1_1") (pintype "passive"))
      (node (ref "U2") (pin "1") (pinfunction "VIN_1") (pintype "power_in"))
      (node (ref "U2") (pin "3") (pinfunction "EN_3") (pintype "input"))
    )
    (net (code "17") (name "GND") (class "Default")
      (node (ref "C1") (pin "1") (pinfunction "1_1") (pintype "passive"))
      (node (ref "C2") (pin "1") (pinfunction "1_1") (pintype "passive"))
      (node (ref "C3") (pin "1") (pinfunction "1_1") (pintype "passive"))
      (node (ref "C4") (pin "2") (pinfunction "2_2") (pintype "passive"))
      (node (ref "C5") (pin "2") (pinfunction "2_2") (pintype "passive"))
      (node (ref "C6") (pin "1") (pinfunction "1_1") (pintype "passive"))
      (node (ref "J1") (pin "A1_B12") (pinfunction "GND_A_A1_B12") (pintype "power_in"))
      (node (ref "J1") (pin "B1_A12") (pinfunction "GND_B_B1_A12") (pintype "power_in"))
      (node (ref "J1") (pin "SH1") (pinfunction "SHIELD_SH1") (pintype "passive"))
      (node (ref "J1") (pin "SH2") (pinfunction "SHIELD_SH2") (pintype "passive"))
      (node (ref "J1") (pin "SH3") (pinfunction "SHIELD_SH3") (pintype "passive"))
      (node (ref "J1") (pin "SH4") (pinfunction "SHIELD_SH4") (pintype "passive"))
      (node (ref "P1") (pin "2") (pinfunction "2_2") (pintype "passive"))
      (node (ref "R37") (pin "1") (pinfunction "1_1") (pintype "passive"))
      (node (ref "R39") (pin "1") (pinfunction "1_1") (pintype "passive"))
      (node (ref "R41") (pin "1") (pinfunction "1_1") (pintype "passive"))
      (node (ref "R43") (pin "1") (pinfunction "1_1") (pintype "passive"))
      (node (ref "R45") (pin "1") (pinfunction "1_1") (pintype "passive"))
      (node (ref "R48") (pin "2") (pinfunction "2_2") (pintype "passive"))
      (node (ref "R49") (pin "1") (pinfunction "1_1") (pintype "passive"))
      (node (ref "S1") (pin "4_1") (pinfunction "GND_4_1") (pintype "passive"))
      (node (ref "S1") (pin "4_2") (pinfunction "GND_4_2") (pintype "passive"))
      (node (ref "S1") (pin "4_3") (pinfunction "GND_4_3") (pintype "passive"))
      (node (ref "S1") (pin "4_4") (pinfunction "GND_4_4") (pintype "passive"))
      (node (ref "S2") (pin "1") (pinfunction "COM_1") (pintype "passive"))
      (node (ref "S2") (pin "2") (pinfunction "COM_2") (pintype "passive"))
      (node (ref "S3") (pin "1") (pinfunction "COM_1") (pintype "passive"))
      (node (ref "S3") (pin "2") (pinfunction "COM_2") (pintype "passive"))
      (node (ref "U1") (pin "19") (pinfunction "GND_19") (pintype "power_in"))
      (node (ref "U1") (pin "20") (pinfunction "GND_20") (pintype "power_in"))
      (node (ref "U1") (pin "21") (pinfunction "GND_21") (pintype "power_in"))
      (node (ref "U1") (pin "22") (pinfunction "GND_22") (pintype "power_in"))
      (node (ref "U1") (pin "23") (pinfunction "GND_23") (pintype "power_in"))
      (node (ref "U1") (pin "24") (pinfunction "GND_24") (pintype "power_in"))
      (node (ref "U1") (pin "25") (pinfunction "GND_25") (pintype "power_in"))
      (node (ref "U1") (pin "26") (pinfunction "GND_26") (pintype "power_in"))
      (node (ref "U1") (pin "27") (pinfunction "GND_27") (pintype "power_in"))
      (node (ref "U1") (pin "28") (pinfunction "GND_28") (pintype "power_in"))
      (node (ref "U1") (pin "29") (pinfunction "GND_29") (pintype "power_in"))
      (node (ref "U1") (pin "30") (pinfunction "GND_30") (pintype "power_in"))
      (node (ref "U1") (pin "31") (pinfunction "GND_31") (pintype "power_in"))
      (node (ref "U1") (pin "32") (pinfunction "GND_32") (pintype "power_in"))
      (node (ref "U1") (pin "33") (pinfunction "GND_33") (pintype "power_in"))
      (node (ref "U1") (pin "34") (pinfunction "GND_34") (pintype "power_in"))
      (node (ref "U1") (pin "35") (pinfunction "GND_35") (pintype "power_in"))
      (node (ref "U1") (pin "36") (pinfunction "GND_36") (pintype "power_in"))
      (node (ref "U1") (pin "37") (pinfunction "GND_37") (pintype "power_in"))
      (node (ref "U1") (pin "38") (pinfunction "GND_38") (pintype "power_in"))
      (node (ref "U1") (pin "39") (pinfunction "GND_39") (pintype "power_in"))
      (node (ref "U1") (pin "9") (pinfunction "GND_9") (pintype "power_in"))
      (node (ref "U2") (pin "2") (pinfunction "GND_2") (pintype "power_in"))
    )
    (net (code "18") (name "Net-(D1-A)") (class "Default")
      (node (ref "D1") (pin "2") (pinfunction "A_2") (pintype "passive"))
      (node (ref "R1") (pin "2") (pinfunction "2_2") (pintype "passive"))
    )
    (net (code "19") (name "Net-(D2-A)") (class "Default")
      (node (ref "D2") (pin "2") (pinfunction "A_2") (pintype "passive"))
      (node (ref "R2") (pin "2") (pinfunction "2_2") (pintype "passive"))
    )
    (net (code "20") (name "Net-(D3-A)") (class "Default")
      (node (ref "D3") (pin "2") (pinfunction "A_2") (pintype "passive"))
      (node (ref "R3") (pin "2") (pinfunction "2_2") (pintype "passive"))
    )
    (net (code "21") (name "Net-(D4-A)") (class "Default")
      (node (ref "D4") (pin "2") (pinfunction "A_2") (pintype "passive"))
      (node (ref "R4") (pin "2") (pinfunction "2_2") (pintype "passive"))
    )
    (net (code "22") (name "Net-(D5-A)") (class "Default")
      (node (ref "D5") (pin "2") (pinfunction "A_2") (pintype "passive"))
      (node (ref "R5") (pin "2") (pinfunction "2_2") (pintype "passive"))
    )
    (net (code "23") (name "Net-(D6-A)") (class "Default")
      (node (ref "D6") (pin "2") (pinfunction "A_2") (pintype "passive"))
      (node (ref "R6") (pin "2") (pinfunction "2_2") (pintype "passive"))
    )
    (net (code "24") (name "Net-(D7-A)") (class "Default")
      (node (ref "D7") (pin "2") (pinfunction "A_2") (pintype "passive"))
      (node (ref "R7") (pin "2") (pinfunction "2_2") (pintype "passive"))
    )
    (net (code "25") (name "Net-(D8-A)") (class "Default")
      (node (ref "D8") (pin "2") (pinfunction "A_2") (pintype "passive"))
      (node (ref "R8") (pin "2") (pinfunction "2_2") (pintype "passive"))
    )
    (net (code "26") (name "Net-(D9-A)") (class "Default")
      (node (ref "D9") (pin "2") (pinfunction "A_2") (pintype "passive"))
      (node (ref "R9") (pin "2") (pinfunction "2_2") (pintype "passive"))
    )
    (net (code "27") (name "Net-(D10-A)") (class "Default")
      (node (ref "D10") (pin "2") (pinfunction "A_2") (pintype "passive"))
      (node (ref "R10") (pin "2") (pinfunction "2_2") (pintype "passive"))
    )
    (net (code "28") (name "Net-(D11-A)") (class "Default")
      (node (ref "D11") (pin "2") (pinfunction "A_2") (pintype "passive"))
      (node (ref "R11") (pin "2") (pinfunction "2_2") (pintype "passive"))
    )
    (net (code "29") (name "Net-(D12-A)") (class "Default")
      (node (ref "D12") (pin "2") (pinfunction "A_2") (pintype "passive"))
      (node (ref "R12") (pin "2") (pinfunction "2_2") (pintype "passive"))
    )
    (net (code "30") (name "Net-(D13-A)") (class "Default")
      (node (ref "D13") (pin "2") (pinfunction "A_2") (pintype "passive"))
      (node (ref "R13") (pin "2") (pinfunction "2_2") (pintype "passive"))
    )
    (net (code "31") (name "Net-(D14-A)") (class "Default")
      (node (ref "D14") (pin "2") (pinfunction "A_2") (pintype "passive"))
      (node (ref "R14") (pin "2") (pinfunction "2_2") (pintype "passive"))
    )
    (net (code "32") (name "Net-(D15-A)") (class "Default")
      (node (ref "D15") (pin "2") (pinfunction "A_2") (pintype "passive"))
      (node (ref "R15") (pin "2") (pinfunction "2_2") (pintype "passive"))
    )
    (net (code "33") (name "Net-(D16-A)") (class "Default")
      (node (ref "D16") (pin "2") (pinfunction "A_2") (pintype "passive"))
      (node (ref "R16") (pin "2") (pinfunction "2_2") (pintype "passive"))
    )
    (net (code "34") (name "Net-(D17-A)") (class "Default")
      (node (ref "D17") (pin "2") (pinfunction "A_2") (pintype "passive"))
      (node (ref "R17") (pin "2") (pinfunction "2_2") (pintype "passive"))
    )
    (net (code "35") (name "Net-(D18-A)") (class "Default")
      (node (ref "D18") (pin "2") (pinfunction "A_2") (pintype "passive"))
      (node (ref "R18") (pin "2") (pinfunction "2_2") (pintype "passive"))
    )
    (net (code "36") (name "Net-(D19-A)") (class "Default")
      (node (ref "D19") (pin "2") (pinfunction "A_2") (pintype "passive"))
      (node (ref "R19") (pin "2") (pinfunction "2_2") (pintype "passive"))
    )
    (net (code "37") (name "Net-(D20-A)") (class "Default")
      (node (ref "D20") (pin "2") (pinfunction "A_2") (pintype "passive"))
      (node (ref "R20") (pin "2") (pinfunction "2_2") (pintype "passive"))
    )
    (net (code "38") (name "Net-(D21-A)") (class "Default")
      (node (ref "D21") (pin "2") (pinfunction "A_2") (pintype "passive"))
      (node (ref "R21") (pin "2") (pinfunction "2_2") (pintype "passive"))
    )
    (net (code "39") (name "Net-(D22-A)") (class "Default")
      (node (ref "D22") (pin "2") (pinfunction "A_2") (pintype "passive"))
      (node (ref "R22") (pin "2") (pinfunction "2_2") (pintype "passive"))
    )
    (net (code "40") (name "Net-(D23-A)") (class "Default")
      (node (ref "D23") (pin "2") (pinfunction "A_2") (pintype "passive"))
      (node (ref "R23") (pin "2") (pinfunction "2_2") (pintype "passive"))
    )
    (net (code "41") (name "Net-(D24-A)") (class "Default")
      (node (ref "D24") (pin "2") (pinfunction "A_2") (pintype "passive"))
      (node (ref "R24") (pin "2") (pinfunction "2_2") (pintype "passive"))
    )
    (net (code "42") (name "Net-(D25-A)") (class "Default")
      (node (ref "D25") (pin "2") (pinfunction "A_2") (pintype "passive"))
      (node (ref "R25") (pin "2") (pinfunction "2_2") (pintype "passive"))
    )
    (net (code "43") (name "Net-(D26-A)") (class "Default")
      (node (ref "D26") (pin "2") (pinfunction "A_2") (pintype "passive"))
      (node (ref "R26") (pin "2") (pinfunction "2_2") (pintype "passive"))
    )
    (net (code "44") (name "Net-(D27-A)") (class "Default")
      (node (ref "D27") (pin "2") (pinfunction "A_2") (pintype "passive"))
      (node (ref "R27") (pin "2") (pinfunction "2_2") (pintype "passive"))
    )
    (net (code "45") (name "Net-(D28-A)") (class "Default")
      (node (ref "D28") (pin "2") (pinfunction "A_2") (pintype "passive"))
      (node (ref "R28") (pin "2") (pinfunction "2_2") (pintype "passive"))
    )
    (net (code "46") (name "Net-(D29-A)") (class "Default")
      (node (ref "D29") (pin "2") (pinfunction "A_2") (pintype "passive"))
      (node (ref "R29") (pin "2") (pinfunction "2_2") (pintype "passive"))
    )
    (net (code "47") (name "Net-(D30-A)") (class "Default")
      (node (ref "D30") (pin "2") (pinfunction "A_2") (pintype "passive"))
      (node (ref "R30") (pin "2") (pinfunction "2_2") (pintype "passive"))
    )
    (net (code "48") (name "Net-(D31-A)") (class "Default")
      (node (ref "D31") (pin "2") (pinfunction "A_2") (pintype "passive"))
      (node (ref "R31") (pin "2") (pinfunction "2_2") (pintype "passive"))
    )
    (net (code "49") (name "Net-(D32-A)") (class "Default")
      (node (ref "D32") (pin "2") (pinfunction "A_2") (pintype "passive"))
      (node (ref "R32") (pin "2") (pinfunction "2_2") (pintype "passive"))
    )
    (net (code "50") (name "Net-(D33-A)") (class "Default")
      (node (ref "D33") (pin "2") (pinfunction "A_2") (pintype "passive"))
      (node (ref "R33") (pin "2") (pinfunction "2_2") (pintype "passive"))
    )
    (net (code "51") (name "Net-(D34-A)") (class "Default")
      (node (ref "D34") (pin "2") (pinfunction "A_2") (pintype "passive"))
      (node (ref "R34") (pin "2") (pinfunction "2_2") (pintype "passive"))
    )
    (net (code "52") (name "Net-(D35-A)") (class "Default")
      (node (ref "D35") (pin "2") (pinfunction "A_2") (pintype "passive"))
      (node (ref "R35") (pin "2") (pinfunction "2_2") (pintype "passive"))
    )
    (net (code "53") (name "Net-(D36-A)") (class "Default")
      (node (ref "D36") (pin "2") (pinfunction "A_2") (pintype "passive"))
      (node (ref "S1") (pin "2") (pinfunction "2_2") (pintype "passive"))
    )
    (net (code "54") (name "Net-(D37-A)") (class "Default")
      (node (ref "D37") (pin "2") (pinfunction "A_2") (pintype "passive"))
      (node (ref "J1") (pin "A4_B9") (pinfunction "VBUS_A_A4_B9") (pintype "power_in"))
      (node (ref "J1") (pin "B4_A9") (pinfunction "VBUS_B_B4_A9") (pintype "power_in"))
    )
    (net (code "55") (name "Net-(J1-CC1)") (class "Default")
      (node (ref "J1") (pin "A5") (pinfunction "CC1_A5") (pintype "bidirectional"))
      (node (ref "R48") (pin "1") (pinfunction "1_1") (pintype "passive"))
    )
    (net (code "56") (name "Net-(J1-CC2)") (class "Default")
      (node (ref "J1") (pin "B5") (pinfunction "CC2_B5") (pintype "bidirectional"))
      (node (ref "R49") (pin "2") (pinfunction "2_2") (pintype "passive"))
    )
    (net (code "57") (name "Net-(P1-Pad1)") (class "Default")
      (node (ref "P1") (pin "1") (pinfunction "1_1") (pintype "passive"))
      (node (ref "S1") (pin "1") (pinfunction "1_1") (pintype "passive"))
    )
    (net (code "58") (name "Net-(Q1-G)") (class "Default")
      (node (ref "Q1") (pin "1") (pinfunction "G_1") (pintype "passive"))
      (node (ref "R36") (pin "2") (pinfunction "2_2") (pintype "passive"))
    )
    (net (code "59") (name "Net-(Q1-S)") (class "Default")
      (node (ref "Q1") (pin "2") (pinfunction "S_2") (pintype "passive"))
      (node (ref "R37") (pin "2") (pinfunction "2_2") (pintype "passive"))
    )
    (net (code "60") (name "Net-(Q2-G)") (class "Default")
      (node (ref "Q2") (pin "1") (pinfunction "G_1") (pintype "passive"))
      (node (ref "R40") (pin "2") (pinfunction "2_2") (pintype "passive"))
    )
    (net (code "61") (name "Net-(Q2-S)") (class "Default")
      (node (ref "Q2") (pin "2") (pinfunction "S_2") (pintype "passive"))
      (node (ref "R41") (pin "2") (pinfunction "2_2") (pintype "passive"))
    )
    (net (code "62") (name "Net-(Q3-G)") (class "Default")
      (node (ref "Q3") (pin "1") (pinfunction "G_1") (pintype "passive"))
      (node (ref "R42") (pin "2") (pinfunction "2_2") (pintype "passive"))
    )
    (net (code "63") (name "Net-(Q3-S)") (class "Default")
      (node (ref "Q3") (pin "2") (pinfunction "S_2") (pintype "passive"))
      (node (ref "R43") (pin "2") (pinfunction "2_2") (pintype "passive"))
    )
    (net (code "64") (name "Net-(Q4-G)") (class "Default")
      (node (ref "Q4") (pin "1") (pinfunction "G_1") (pintype "passive"))
      (node (ref "R38") (pin "2") (pinfunction "2_2") (pintype "passive"))
    )
    (net (code "65") (name "Net-(Q4-S)") (class "Default")
      (node (ref "Q4") (pin "2") (pinfunction "S_2") (pintype "passive"))
      (node (ref "R39") (pin "2") (pinfunction "2_2") (pintype "passive"))
    )
    (net (code "66") (name "Net-(Q5-G)") (class "Default")
      (node (ref "Q5") (pin "1") (pinfunction "G_1") (pintype "passive"))
      (node (ref "R44") (pin "2") (pinfunction "2_2") (pintype "passive"))
    )
    (net (code "67") (name "Net-(Q5-S)") (class "Default")
      (node (ref "Q5") (pin "2") (pinfunction "S_2") (pintype "passive"))
      (node (ref "R45") (pin "2") (pinfunction "2_2") (pintype "passive"))
    )
    (net (code "68") (name "Net-(R47-Pad2)") (class "Default")
      (node (ref "R47") (pin "2") (pinfunction "2_2") (pintype "passive"))
      (node (ref "S3") (pin "3") (pinfunction "NO_3") (pintype "passive"))
      (node (ref "S3") (pin "4") (pinfunction "NO_4") (pintype "passive"))
    )
    (net (code "69") (name "unconnected-(J1-SBU1-PadA8)") (class "Default")
      (node (ref "J1") (pin "A8") (pinfunction "SBU1_A8") (pintype "bidirectional"))
    )
    (net (code "70") (name "unconnected-(J1-SBU2-PadB8)") (class "Default")
      (node (ref "J1") (pin "B8") (pinfunction "SBU2_B8") (pintype "bidirectional"))
    )
    (net (code "71") (name "unconnected-(S1-Pad3)") (class "Default")
      (node (ref "S1") (pin "3") (pinfunction "3_3") (pintype "passive"))
    )
    (net (code "72") (name "unconnected-(U1-IO5-Pad4)") (class "Default")
      (node (ref "U1") (pin "4") (pinfunction "IO5_4") (pintype "bidirectional"))
    )
    (net (code "73") (name "unconnected-(U1-IO6-Pad5)") (class "Default")
      (node (ref "U1") (pin "5") (pinfunction "IO6_5") (pintype "bidirectional"))
    )
    (net (code "74") (name "unconnected-(U1-IO7-Pad6)") (class "Default")
      (node (ref "U1") (pin "6") (pinfunction "IO7_6") (pintype "bidirectional"))
    )
    (net (code "75") (name "unconnected-(U1-IO8-Pad7)") (class "Default")
      (node (ref "U1") (pin "7") (pinfunction "IO8_7") (pintype "bidirectional"))
    )
    (net (code "76") (name "unconnected-(U1-IO10-Pad10)") (class "Default")
      (node (ref "U1") (pin "10") (pinfunction "IO10_10") (pintype "bidirectional"))
    )
    (net (code "77") (name "unconnected-(U1-RXD-Pad11)") (class "Default")
      (node (ref "U1") (pin "11") (pinfunction "RXD_11") (pintype "bidirectional"))
    )
    (net (code "78") (name "unconnected-(U1-TXD-Pad12)") (class "Default")
      (node (ref "U1") (pin "12") (pinfunction "TXD_12") (pintype "bidirectional"))
    )
    (net (code "79") (name "unconnected-(U2-NC-Pad4)") (class "Default")
      (node (ref "U2") (pin "4") (pinfunction "NC_4") (pintype "passive"))
    )
  )
)
